# Controller.net
KiCad netlist of a schematic drawn in Altium Designer
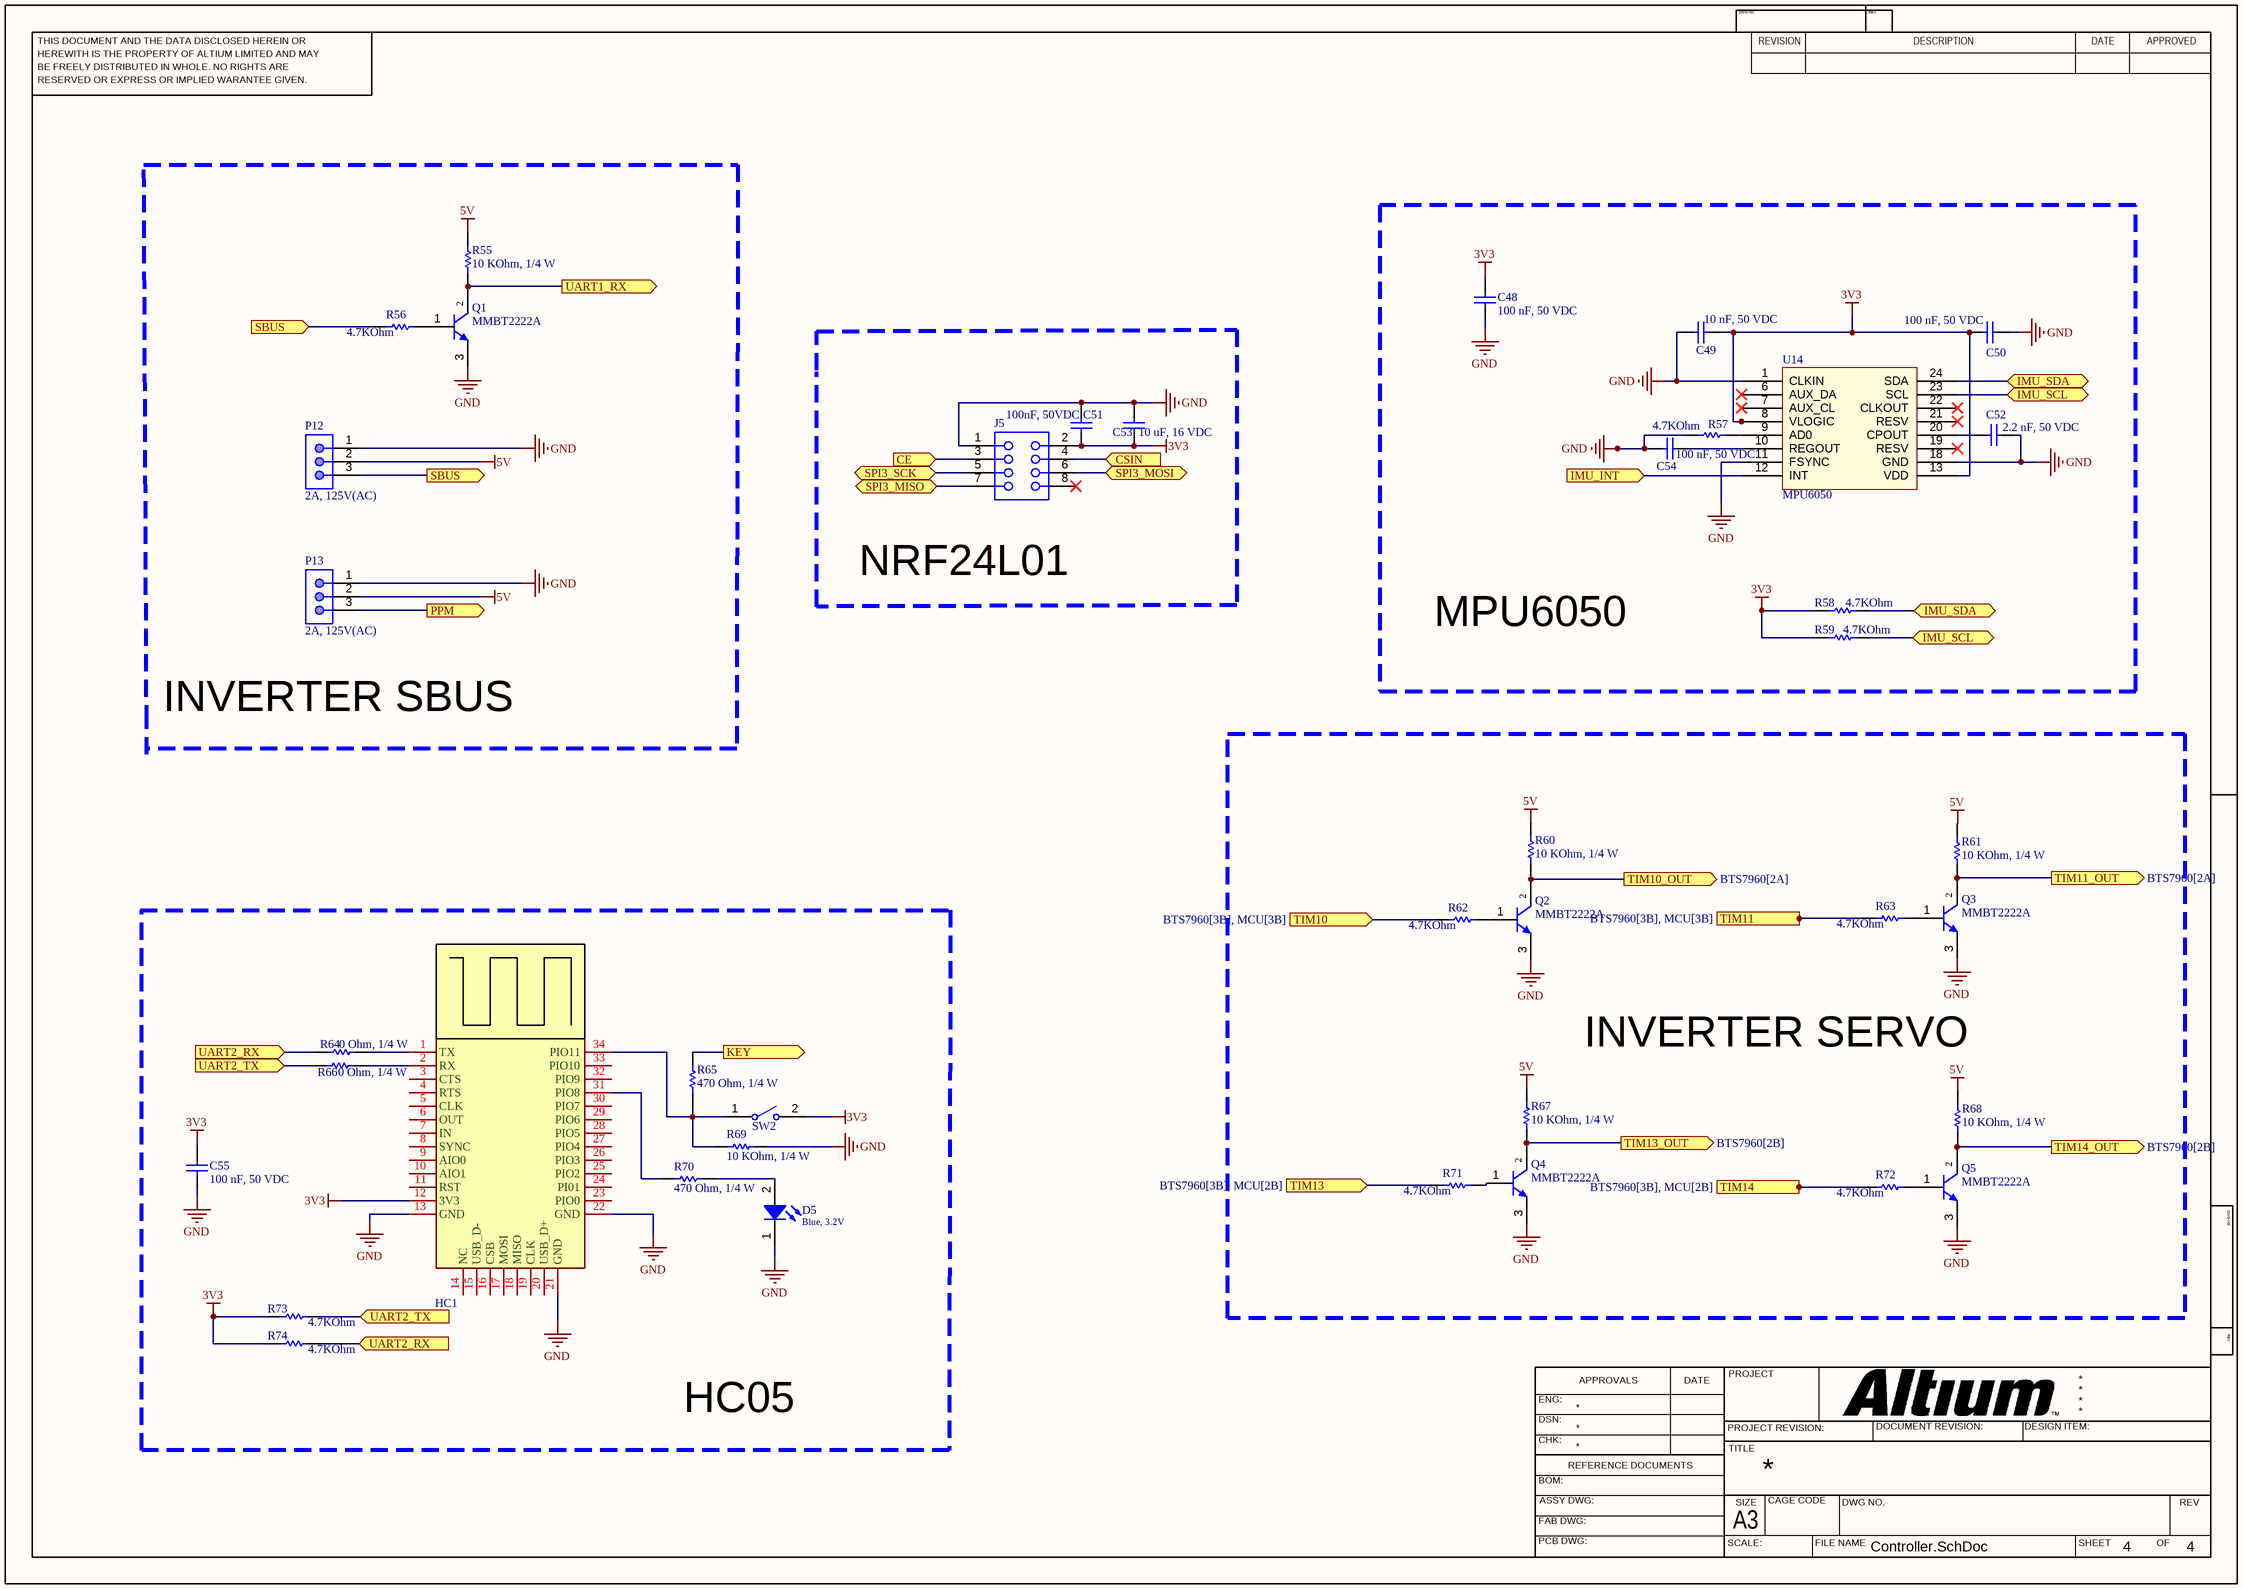
[diagram p0: Controller.SchDoc]

(export (version "E")
  (design (tool "Eeschema 10.0.6"))
  (components
    (comp (ref "C48")
      (value "100 nF, 50 VDC")
      (footprint "CAP_0603")
      (description "CAP, size 0603, 100 nF, 50 VDC")
      (fields (field (name "TOLERANCE") "+/-10%"))
      (libsource (lib "Altium_Ceramic_Cap") (part "0106031041050"))
    )
    (comp (ref "C49")
      (value "10 nF, 50 VDC")
      (footprint "CAP_0603")
      (description "CAP, size 0603, 10 nF, 50 VDC")
      (fields (field (name "TOLERANCE") "+/-5%"))
      (libsource (lib "Altium_Ceramic_Cap") (part "0106031030550"))
    )
    (comp (ref "C50")
      (value "100 nF, 50 VDC")
      (footprint "CAP_0603")
      (description "CAP, size 0603, 100 nF, 50 VDC")
      (fields (field (name "TOLERANCE") "+/-10%"))
      (libsource (lib "Altium_Ceramic_Cap") (part "0106031041050"))
    )
    (comp (ref "C51")
      (value "100nF, 50VDC")
      (footprint "CAP_0805")
      (description "CAP, size 0805, 150 nF, 50 VDC")
      (fields (field (name "TOLERANCE") "+/-10%"))
      (libsource (lib "Altium_Ceramic_Cap") (part "0108051541050"))
    )
    (comp (ref "C52")
      (value "2.2 nF, 50 VDC")
      (footprint "CAP_0603")
      (description "CAP, size 0603, 2.2 nF, 50 VDC")
      (fields (field (name "TOLERANCE") "+/-5%"))
      (libsource (lib "Altium_Ceramic_Cap") (part "0106032220550"))
    )
    (comp (ref "C53")
      (value "10 uF, 16 VDC")
      (footprint "CAP_0805")
      (description "CAP, size 0805, 10 uF, 16 VDC")
      (fields (field (name "TOLERANCE") "+/-10%"))
      (libsource (lib "Altium_Ceramic_Cap") (part "0108051061016"))
    )
    (comp (ref "C54")
      (value "100 nF, 50 VDC")
      (footprint "CAP_0603")
      (description "CAP, size 0603, 100 nF, 50 VDC")
      (fields (field (name "TOLERANCE") "+/-10%"))
      (libsource (lib "Altium_Ceramic_Cap") (part "0106031041050"))
    )
    (comp (ref "C55")
      (value "100 nF, 50 VDC")
      (footprint "CAP_0603")
      (description "CAP, size 0603, 100 nF, 50 VDC")
      (fields (field (name "TOLERANCE") "+/-10%"))
      (libsource (lib "Altium_Ceramic_Cap") (part "0106031041050"))
    )
    (comp (ref "D5")
      (value "Blue, 3.2V")
      (footprint "WL-SMCW_0603_H=0.7mm")
      (description "WL-SMCW SMT Mono-color Chip LED Blur, size 0603, Blue, 3.2V, 140deg")
      (libsource (lib "Altium_LED") (part "160603BlueBlur"))
    )
    (comp (ref "HC1") (value "HC05") (footprint "PCBComponent_1") (libsource (lib "HC05_Sche") (part "HC05")))
    (comp (ref "J5")
      (value "61300821821")
      (footprint "61300821821")
      (description "WR-PHD Socket Header, THT, pitch 2.54mm, Dual Row, Vertical, 8p")
      (fields (field (name "MANUFACTURER") "Wurth Elektronik"))
      (libsource (lib "Altium_Header") (part "61300821821"))
    )
    (comp (ref "P12")
      (value "2A, 125V(AC)")
      (footprint "62000311622")
      (description "WR-WTB Male Vertical Shrouded Header, pitch 2mm, 3p")
      (fields (field (name "PART NUMBER") "62000311622") (field (name "PUBLISHER") "Wurth Elektronik"))
      (libsource (lib "Altium_PCB_Connector") (part "62000311622"))
    )
    (comp (ref "P13")
      (value "2A, 125V(AC)")
      (footprint "62000311622")
      (description "WR-WTB Male Vertical Shrouded Header, pitch 2mm, 3p")
      (fields (field (name "PART NUMBER") "62000311622") (field (name "PUBLISHER") "Wurth Elektronik"))
      (libsource (lib "Altium_PCB_Connector") (part "62000311622"))
    )
    (comp (ref "Q1")
      (value "MMBT2222A")
      (footprint "MMBT-SOT23")
      (description "TRANS NPN, 40V, 600MA, SOT23-3")
      (libsource (lib "Altium_BJT") (part "MMBT2222A"))
    )
    (comp (ref "Q2")
      (value "MMBT2222A")
      (footprint "MMBT-SOT23")
      (description "TRANS NPN, 40V, 600MA, SOT23-3")
      (libsource (lib "Altium_BJT") (part "MMBT2222A"))
    )
    (comp (ref "Q3")
      (value "MMBT2222A")
      (footprint "MMBT-SOT23")
      (description "TRANS NPN, 40V, 600MA, SOT23-3")
      (libsource (lib "Altium_BJT") (part "MMBT2222A"))
    )
    (comp (ref "Q4")
      (value "MMBT2222A")
      (footprint "MMBT-SOT23")
      (description "TRANS NPN, 40V, 600MA, SOT23-3")
      (libsource (lib "Altium_BJT") (part "MMBT2222A"))
    )
    (comp (ref "Q5")
      (value "MMBT2222A")
      (footprint "MMBT-SOT23")
      (description "TRANS NPN, 40V, 600MA, SOT23-3")
      (libsource (lib "Altium_BJT") (part "MMBT2222A"))
    )
    (comp (ref "R55")
      (value "10 KOhm, 1/4 W")
      (footprint "resistor_0603")
      (description "RES, size 0603, 10 KOhm, 1/4 W")
      (libsource (lib "Altium_Resistor") (part "0006031031"))
    )
    (comp (ref "R56")
      (value "4.7KOhm")
      (footprint "resistor_0603")
      (description "RES, size 0603, 4.7 MOhm, 1/4 W")
      (libsource (lib "Altium_Resistor") (part "0006034755"))
    )
    (comp (ref "R57")
      (value "4.7KOhm")
      (footprint "resistor_0603")
      (description "RES, size 0603, 4.4 KOhm, 1/4 W")
      (libsource (lib "Altium_Resistor") (part "0006034425"))
    )
    (comp (ref "R58")
      (value "4.7KOhm")
      (footprint "resistor_0603")
      (description "RES, size 0603, 4.4 KOhm, 1/4 W")
      (libsource (lib "Altium_Resistor") (part "0006034425"))
    )
    (comp (ref "R59")
      (value "4.7KOhm")
      (footprint "resistor_0603")
      (description "RES, size 0603, 4.4 KOhm, 1/4 W")
      (libsource (lib "Altium_Resistor") (part "0006034425"))
    )
    (comp (ref "R60")
      (value "10 KOhm, 1/4 W")
      (footprint "resistor_0603")
      (description "RES, size 0603, 10 KOhm, 1/4 W")
      (libsource (lib "Altium_Resistor") (part "0006031031"))
    )
    (comp (ref "R61")
      (value "10 KOhm, 1/4 W")
      (footprint "resistor_0603")
      (description "RES, size 0603, 10 KOhm, 1/4 W")
      (libsource (lib "Altium_Resistor") (part "0006031031"))
    )
    (comp (ref "R62")
      (value "4.7KOhm")
      (footprint "resistor_0603")
      (description "RES, size 0603, 4.7 MOhm, 1/4 W")
      (libsource (lib "Altium_Resistor") (part "0006034755"))
    )
    (comp (ref "R63")
      (value "4.7KOhm")
      (footprint "resistor_0603")
      (description "RES, size 0603, 4.7 MOhm, 1/4 W")
      (libsource (lib "Altium_Resistor") (part "0006034755"))
    )
    (comp (ref "R64")
      (value "0 Ohm, 1/4 W")
      (footprint "resistor_0603")
      (description "RES, size 0603, 0 Ohm, 1/4 W")
      (libsource (lib "Altium_Resistor") (part "0006030001"))
    )
    (comp (ref "R65")
      (value "470 Ohm, 1/4 W")
      (footprint "resistor_0603")
      (description "RES, size 0603, 470 Ohm, 1/4 W")
      (libsource (lib "Altium_Resistor") (part "0006034711"))
    )
    (comp (ref "R66")
      (value "0 Ohm, 1/4 W")
      (footprint "resistor_0603")
      (description "RES, size 0603, 0 Ohm, 1/4 W")
      (libsource (lib "Altium_Resistor") (part "0006030005"))
    )
    (comp (ref "R67")
      (value "10 KOhm, 1/4 W")
      (footprint "resistor_0603")
      (description "RES, size 0603, 10 KOhm, 1/4 W")
      (libsource (lib "Altium_Resistor") (part "0006031031"))
    )
    (comp (ref "R68")
      (value "10 KOhm, 1/4 W")
      (footprint "resistor_0603")
      (description "RES, size 0603, 10 KOhm, 1/4 W")
      (libsource (lib "Altium_Resistor") (part "0006031031"))
    )
    (comp (ref "R69")
      (value "10 KOhm, 1/4 W")
      (footprint "resistor_0603")
      (description "RES, size 0603, 10 KOhm, 1/4 W")
      (libsource (lib "Altium_Resistor") (part "0006031031"))
    )
    (comp (ref "R70")
      (value "470 Ohm, 1/4 W")
      (footprint "resistor_0603")
      (description "RES, size 0603, 470 Ohm, 1/4 W")
      (libsource (lib "Altium_Resistor") (part "0006034711"))
    )
    (comp (ref "R71")
      (value "4.7KOhm")
      (footprint "resistor_0603")
      (description "RES, size 0603, 4.7 MOhm, 1/4 W")
      (libsource (lib "Altium_Resistor") (part "0006034755"))
    )
    (comp (ref "R72")
      (value "4.7KOhm")
      (footprint "resistor_0603")
      (description "RES, size 0603, 4.7 MOhm, 1/4 W")
      (libsource (lib "Altium_Resistor") (part "0006034755"))
    )
    (comp (ref "R73")
      (value "4.7KOhm")
      (footprint "resistor_0603")
      (description "RES, size 0603, 4.4 KOhm, 1/4 W")
      (libsource (lib "Altium_Resistor") (part "0006034425"))
    )
    (comp (ref "R74")
      (value "4.7KOhm")
      (footprint "resistor_0603")
      (description "RES, size 0603, 4.4 KOhm, 1/4 W")
      (libsource (lib "Altium_Resistor") (part "0006034425"))
    )
    (comp (ref "SW2")
      (value "TS-1101-C-W")
      (footprint "TS-1101-C-W")
      (description "Tact Switch, L6 x W3.8 x H2.5mm, 260g, SPST-NO, 12V, 50mA")
      (fields
        (field (name "MANUFACTURER") "Wurth Elektronik")
        (field (name "LCSC PART #") "XKB Connectivity")
      )
      (libsource (lib "Altium_Button") (part "TS-1101-C-W"))
    )
    (comp (ref "U14")
      (value "MPU6050")
      (footprint "IS-QFN-24_V")
      (libsource (lib "Devzone_SCHLib") (part "MPU6050"))
    )
  )
  (nets
    (net (code "1") (name "/CE") (class "Default")
      (node (ref "J5") (pin "3") (pinfunction "3_3") (pintype "passive"))
    )
    (net (code "2") (name "/CSIN") (class "Default")
      (node (ref "J5") (pin "4") (pinfunction "4_4") (pintype "passive"))
    )
    (net (code "3") (name "/IMU_INT") (class "Default")
      (node (ref "U14") (pin "12") (pinfunction "INT_12") (pintype "passive"))
    )
    (net (code "4") (name "/IMU_SCL") (class "Default")
      (node (ref "R59") (pin "2") (pinfunction "2_2") (pintype "passive"))
      (node (ref "U14") (pin "23") (pinfunction "SCL_23") (pintype "passive"))
    )
    (net (code "5") (name "/IMU_SDA") (class "Default")
      (node (ref "R58") (pin "1") (pinfunction "1_1") (pintype "passive"))
      (node (ref "U14") (pin "24") (pinfunction "SDA_24") (pintype "passive"))
    )
    (net (code "6") (name "/KEY") (class "Default")
      (node (ref "R65") (pin "2") (pinfunction "2_2") (pintype "passive"))
    )
    (net (code "7") (name "/PPM") (class "Default")
      (node (ref "P13") (pin "3") (pinfunction "3_3") (pintype "passive"))
    )
    (net (code "8") (name "/SBUS") (class "Default")
      (node (ref "P12") (pin "3") (pinfunction "3_3") (pintype "passive"))
      (node (ref "R56") (pin "1") (pinfunction "1_1") (pintype "passive"))
    )
    (net (code "9") (name "/SPI3_MISO") (class "Default")
      (node (ref "J5") (pin "7") (pinfunction "7_7") (pintype "passive"))
    )
    (net (code "10") (name "/SPI3_MOSI") (class "Default")
      (node (ref "J5") (pin "6") (pinfunction "6_6") (pintype "passive"))
    )
    (net (code "11") (name "/SPI3_SCK") (class "Default")
      (node (ref "J5") (pin "5") (pinfunction "5_5") (pintype "passive"))
    )
    (net (code "12") (name "/TIM10") (class "Default")
      (node (ref "R62") (pin "1") (pinfunction "1_1") (pintype "passive"))
    )
    (net (code "13") (name "/TIM10_OUT") (class "Default")
      (node (ref "Q2") (pin "2") (pinfunction "C_2") (pintype "passive"))
      (node (ref "R60") (pin "1") (pinfunction "1_1") (pintype "passive"))
    )
    (net (code "14") (name "/TIM11") (class "Default")
      (node (ref "R63") (pin "1") (pinfunction "1_1") (pintype "passive"))
    )
    (net (code "15") (name "/TIM11_OUT") (class "Default")
      (node (ref "Q3") (pin "2") (pinfunction "C_2") (pintype "passive"))
      (node (ref "R61") (pin "1") (pinfunction "1_1") (pintype "passive"))
    )
    (net (code "16") (name "/TIM13") (class "Default")
      (node (ref "R71") (pin "1") (pinfunction "1_1") (pintype "passive"))
    )
    (net (code "17") (name "/TIM13_OUT") (class "Default")
      (node (ref "Q4") (pin "2") (pinfunction "C_2") (pintype "passive"))
      (node (ref "R67") (pin "1") (pinfunction "1_1") (pintype "passive"))
    )
    (net (code "18") (name "/TIM14") (class "Default")
      (node (ref "R72") (pin "1") (pinfunction "1_1") (pintype "passive"))
    )
    (net (code "19") (name "/TIM14_OUT") (class "Default")
      (node (ref "Q5") (pin "2") (pinfunction "C_2") (pintype "passive"))
      (node (ref "R68") (pin "1") (pinfunction "1_1") (pintype "passive"))
    )
    (net (code "20") (name "/UART1_RX") (class "Default")
      (node (ref "Q1") (pin "2") (pinfunction "C_2") (pintype "passive"))
      (node (ref "R55") (pin "1") (pinfunction "1_1") (pintype "passive"))
    )
    (net (code "21") (name "/UART2_RX") (class "Default")
      (node (ref "R64") (pin "1") (pinfunction "1_1") (pintype "passive"))
      (node (ref "R74") (pin "2") (pinfunction "2_2") (pintype "passive"))
    )
    (net (code "22") (name "/UART2_TX") (class "Default")
      (node (ref "R66") (pin "1") (pinfunction "1_1") (pintype "passive"))
      (node (ref "R73") (pin "1") (pinfunction "1_1") (pintype "passive"))
    )
    (net (code "23") (name "3V3") (class "Default")
      (node (ref "C48") (pin "1") (pinfunction "1_1") (pintype "passive"))
      (node (ref "C49") (pin "2") (pinfunction "2_2") (pintype "passive"))
      (node (ref "C50") (pin "1") (pinfunction "1_1") (pintype "passive"))
      (node (ref "C51") (pin "1") (pinfunction "1_1") (pintype "passive"))
      (node (ref "C53") (pin "1") (pinfunction "1_1") (pintype "passive"))
      (node (ref "C55") (pin "1") (pinfunction "1_1") (pintype "passive"))
      (node (ref "HC1") (pin "12") (pinfunction "3V3_12") (pintype "passive"))
      (node (ref "J5") (pin "2") (pinfunction "2_2") (pintype "passive"))
      (node (ref "R58") (pin "2") (pinfunction "2_2") (pintype "passive"))
      (node (ref "R59") (pin "1") (pinfunction "1_1") (pintype "passive"))
      (node (ref "R73") (pin "2") (pinfunction "2_2") (pintype "passive"))
      (node (ref "R74") (pin "1") (pinfunction "1_1") (pintype "passive"))
      (node (ref "SW2") (pin "2") (pinfunction "2_2") (pintype "passive"))
      (node (ref "U14") (pin "13") (pinfunction "VDD_13") (pintype "passive"))
      (node (ref "U14") (pin "8") (pinfunction "VLOGIC_8") (pintype "passive"))
    )
    (net (code "24") (name "5V") (class "Default")
      (node (ref "P12") (pin "2") (pinfunction "2_2") (pintype "passive"))
      (node (ref "P13") (pin "2") (pinfunction "2_2") (pintype "passive"))
      (node (ref "R55") (pin "2") (pinfunction "2_2") (pintype "passive"))
      (node (ref "R60") (pin "2") (pinfunction "2_2") (pintype "passive"))
      (node (ref "R61") (pin "2") (pinfunction "2_2") (pintype "passive"))
      (node (ref "R67") (pin "2") (pinfunction "2_2") (pintype "passive"))
      (node (ref "R68") (pin "2") (pinfunction "2_2") (pintype "passive"))
    )
    (net (code "25") (name "GND") (class "Default")
      (node (ref "C48") (pin "2") (pinfunction "2_2") (pintype "passive"))
      (node (ref "C49") (pin "1") (pinfunction "1_1") (pintype "passive"))
      (node (ref "C50") (pin "2") (pinfunction "2_2") (pintype "passive"))
      (node (ref "C51") (pin "2") (pinfunction "2_2") (pintype "passive"))
      (node (ref "C52") (pin "1") (pinfunction "1_1") (pintype "passive"))
      (node (ref "C53") (pin "2") (pinfunction "2_2") (pintype "passive"))
      (node (ref "C54") (pin "1") (pinfunction "1_1") (pintype "passive"))
      (node (ref "C55") (pin "2") (pinfunction "2_2") (pintype "passive"))
      (node (ref "D5") (pin "1") (pinfunction "K_1") (pintype "passive"))
      (node (ref "HC1") (pin "13") (pinfunction "GND_13") (pintype "passive"))
      (node (ref "HC1") (pin "21") (pinfunction "GND_21") (pintype "passive"))
      (node (ref "HC1") (pin "22") (pinfunction "GND_22") (pintype "passive"))
      (node (ref "J5") (pin "1") (pinfunction "1_1") (pintype "passive"))
      (node (ref "P12") (pin "1") (pinfunction "1_1") (pintype "passive"))
      (node (ref "P13") (pin "1") (pinfunction "1_1") (pintype "passive"))
      (node (ref "Q1") (pin "3") (pinfunction "E_3") (pintype "passive"))
      (node (ref "Q2") (pin "3") (pinfunction "E_3") (pintype "passive"))
      (node (ref "Q3") (pin "3") (pinfunction "E_3") (pintype "passive"))
      (node (ref "Q4") (pin "3") (pinfunction "E_3") (pintype "passive"))
      (node (ref "Q5") (pin "3") (pinfunction "E_3") (pintype "passive"))
      (node (ref "R57") (pin "2") (pinfunction "2_2") (pintype "passive"))
      (node (ref "R69") (pin "2") (pinfunction "2_2") (pintype "passive"))
      (node (ref "U14") (pin "1") (pinfunction "CLKIN_1") (pintype "passive"))
      (node (ref "U14") (pin "11") (pinfunction "FSYNC_11") (pintype "passive"))
      (node (ref "U14") (pin "18") (pinfunction "GND_18") (pintype "passive"))
    )
    (net (code "26") (name "Net-(D5-A)") (class "Default")
      (node (ref "D5") (pin "2") (pinfunction "A_2") (pintype "passive"))
      (node (ref "R70") (pin "2") (pinfunction "2_2") (pintype "passive"))
    )
    (net (code "27") (name "Net-(HC1-PIO8)") (class "Default")
      (node (ref "HC1") (pin "31") (pinfunction "PIO8_31") (pintype "passive"))
      (node (ref "R70") (pin "1") (pinfunction "1_1") (pintype "passive"))
    )
    (net (code "28") (name "Net-(HC1-PIO11)") (class "Default")
      (node (ref "HC1") (pin "34") (pinfunction "PIO11_34") (pintype "passive"))
      (node (ref "R65") (pin "1") (pinfunction "1_1") (pintype "passive"))
      (node (ref "R69") (pin "1") (pinfunction "1_1") (pintype "passive"))
      (node (ref "SW2") (pin "1") (pinfunction "1_1") (pintype "passive"))
    )
    (net (code "29") (name "Net-(HC1-RX)") (class "Default")
      (node (ref "HC1") (pin "2") (pinfunction "RX_2") (pintype "passive"))
      (node (ref "R66") (pin "2") (pinfunction "2_2") (pintype "passive"))
    )
    (net (code "30") (name "Net-(HC1-TX)") (class "Default")
      (node (ref "HC1") (pin "1") (pinfunction "TX_1") (pintype "passive"))
      (node (ref "R64") (pin "2") (pinfunction "2_2") (pintype "passive"))
    )
    (net (code "31") (name "Net-(Q1-B)") (class "Default")
      (node (ref "Q1") (pin "1") (pinfunction "B_1") (pintype "passive"))
      (node (ref "R56") (pin "2") (pinfunction "2_2") (pintype "passive"))
    )
    (net (code "32") (name "Net-(Q2-B)") (class "Default")
      (node (ref "Q2") (pin "1") (pinfunction "B_1") (pintype "passive"))
      (node (ref "R62") (pin "2") (pinfunction "2_2") (pintype "passive"))
    )
    (net (code "33") (name "Net-(Q3-B)") (class "Default")
      (node (ref "Q3") (pin "1") (pinfunction "B_1") (pintype "passive"))
      (node (ref "R63") (pin "2") (pinfunction "2_2") (pintype "passive"))
    )
    (net (code "34") (name "Net-(Q4-B)") (class "Default")
      (node (ref "Q4") (pin "1") (pinfunction "B_1") (pintype "passive"))
      (node (ref "R71") (pin "2") (pinfunction "2_2") (pintype "passive"))
    )
    (net (code "35") (name "Net-(Q5-B)") (class "Default")
      (node (ref "Q5") (pin "1") (pinfunction "B_1") (pintype "passive"))
      (node (ref "R72") (pin "2") (pinfunction "2_2") (pintype "passive"))
    )
    (net (code "36") (name "Net-(U14-AD0)") (class "Default")
      (node (ref "R57") (pin "1") (pinfunction "1_1") (pintype "passive"))
      (node (ref "U14") (pin "9") (pinfunction "AD0_9") (pintype "passive"))
    )
    (net (code "37") (name "Net-(U14-CPOUT)") (class "Default")
      (node (ref "C52") (pin "2") (pinfunction "2_2") (pintype "passive"))
      (node (ref "U14") (pin "20") (pinfunction "CPOUT_20") (pintype "passive"))
    )
    (net (code "38") (name "Net-(U14-REGOUT)") (class "Default")
      (node (ref "C54") (pin "2") (pinfunction "2_2") (pintype "passive"))
      (node (ref "U14") (pin "10") (pinfunction "REGOUT_10") (pintype "passive"))
    )
    (net (code "39") (name "unconnected-(HC1-AIO0-Pad9)") (class "Default")
      (node (ref "HC1") (pin "9") (pinfunction "AIO0_9") (pintype "passive"))
    )
    (net (code "40") (name "unconnected-(HC1-AIO1-Pad10)") (class "Default")
      (node (ref "HC1") (pin "10") (pinfunction "AIO1_10") (pintype "passive"))
    )
    (net (code "41") (name "unconnected-(HC1-CLK-Pad5)") (class "Default")
      (node (ref "HC1") (pin "5") (pinfunction "CLK_5") (pintype "passive"))
    )
    (net (code "42") (name "unconnected-(HC1-CLK-Pad19)") (class "Default")
      (node (ref "HC1") (pin "19") (pinfunction "CLK_19") (pintype "passive"))
    )
    (net (code "43") (name "unconnected-(HC1-CSB-Pad16)") (class "Default")
      (node (ref "HC1") (pin "16") (pinfunction "CSB_16") (pintype "passive"))
    )
    (net (code "44") (name "unconnected-(HC1-CTS-Pad3)") (class "Default")
      (node (ref "HC1") (pin "3") (pinfunction "CTS_3") (pintype "passive"))
    )
    (net (code "45") (name "unconnected-(HC1-IN-Pad7)") (class "Default")
      (node (ref "HC1") (pin "7") (pinfunction "IN_7") (pintype "passive"))
    )
    (net (code "46") (name "unconnected-(HC1-MISO-Pad18)") (class "Default")
      (node (ref "HC1") (pin "18") (pinfunction "MISO_18") (pintype "passive"))
    )
    (net (code "47") (name "unconnected-(HC1-MOSI-Pad17)") (class "Default")
      (node (ref "HC1") (pin "17") (pinfunction "MOSI_17") (pintype "passive"))
    )
    (net (code "48") (name "unconnected-(HC1-NC-Pad14)") (class "Default")
      (node (ref "HC1") (pin "14") (pinfunction "NC_14") (pintype "passive"))
    )
    (net (code "49") (name "unconnected-(HC1-OUT-Pad6)") (class "Default")
      (node (ref "HC1") (pin "6") (pinfunction "OUT_6") (pintype "passive"))
    )
    (net (code "50") (name "unconnected-(HC1-PI01-Pad24)") (class "Default")
      (node (ref "HC1") (pin "24") (pinfunction "PI01_24") (pintype "passive"))
    )
    (net (code "51") (name "unconnected-(HC1-PIO0-Pad23)") (class "Default")
      (node (ref "HC1") (pin "23") (pinfunction "PIO0_23") (pintype "passive"))
    )
    (net (code "52") (name "unconnected-(HC1-PIO2-Pad25)") (class "Default")
      (node (ref "HC1") (pin "25") (pinfunction "PIO2_25") (pintype "passive"))
    )
    (net (code "53") (name "unconnected-(HC1-PIO3-Pad26)") (class "Default")
      (node (ref "HC1") (pin "26") (pinfunction "PIO3_26") (pintype "passive"))
    )
    (net (code "54") (name "unconnected-(HC1-PIO4-Pad27)") (class "Default")
      (node (ref "HC1") (pin "27") (pinfunction "PIO4_27") (pintype "passive"))
    )
    (net (code "55") (name "unconnected-(HC1-PIO5-Pad28)") (class "Default")
      (node (ref "HC1") (pin "28") (pinfunction "PIO5_28") (pintype "passive"))
    )
    (net (code "56") (name "unconnected-(HC1-PIO6-Pad29)") (class "Default")
      (node (ref "HC1") (pin "29") (pinfunction "PIO6_29") (pintype "passive"))
    )
    (net (code "57") (name "unconnected-(HC1-PIO7-Pad30)") (class "Default")
      (node (ref "HC1") (pin "30") (pinfunction "PIO7_30") (pintype "passive"))
    )
    (net (code "58") (name "unconnected-(HC1-PIO9-Pad32)") (class "Default")
      (node (ref "HC1") (pin "32") (pinfunction "PIO9_32") (pintype "passive"))
    )
    (net (code "59") (name "unconnected-(HC1-PIO10-Pad33)") (class "Default")
      (node (ref "HC1") (pin "33") (pinfunction "PIO10_33") (pintype "passive"))
    )
    (net (code "60") (name "unconnected-(HC1-RST-Pad11)") (class "Default")
      (node (ref "HC1") (pin "11") (pinfunction "RST_11") (pintype "passive"))
    )
    (net (code "61") (name "unconnected-(HC1-RTS-Pad4)") (class "Default")
      (node (ref "HC1") (pin "4") (pinfunction "RTS_4") (pintype "passive"))
    )
    (net (code "62") (name "unconnected-(HC1-SYNC-Pad8)") (class "Default")
      (node (ref "HC1") (pin "8") (pinfunction "SYNC_8") (pintype "passive"))
    )
    (net (code "63") (name "unconnected-(HC1-USB_D+-Pad20)") (class "Default")
      (node (ref "HC1") (pin "20") (pinfunction "USB_D+_20") (pintype "passive"))
    )
    (net (code "64") (name "unconnected-(HC1-USB_D--Pad15)") (class "Default")
      (node (ref "HC1") (pin "15") (pinfunction "USB_D-_15") (pintype "passive"))
    )
    (net (code "65") (name "unconnected-(J5-Pad8)") (class "Default")
      (node (ref "J5") (pin "8") (pinfunction "8_8") (pintype "passive+no_connect"))
    )
    (net (code "66") (name "unconnected-(U14-AUX_CL-Pad7)") (class "Default")
      (node (ref "U14") (pin "7") (pinfunction "AUX_CL_7") (pintype "passive+no_connect"))
    )
    (net (code "67") (name "unconnected-(U14-AUX_DA-Pad6)") (class "Default")
      (node (ref "U14") (pin "6") (pinfunction "AUX_DA_6") (pintype "passive+no_connect"))
    )
    (net (code "68") (name "unconnected-(U14-CLKOUT-Pad22)") (class "Default")
      (node (ref "U14") (pin "22") (pinfunction "CLKOUT_22") (pintype "passive+no_connect"))
    )
    (net (code "69") (name "unconnected-(U14-RESV-Pad19)") (class "Default")
      (node (ref "U14") (pin "19") (pinfunction "RESV_19") (pintype "passive+no_connect"))
    )
    (net (code "70") (name "unconnected-(U14-RESV-Pad21)") (class "Default")
      (node (ref "U14") (pin "21") (pinfunction "RESV_21") (pintype "passive+no_connect"))
    )
  )
)
